# SM3.net
KiCad netlist of a schematic drawn in Altium Designer
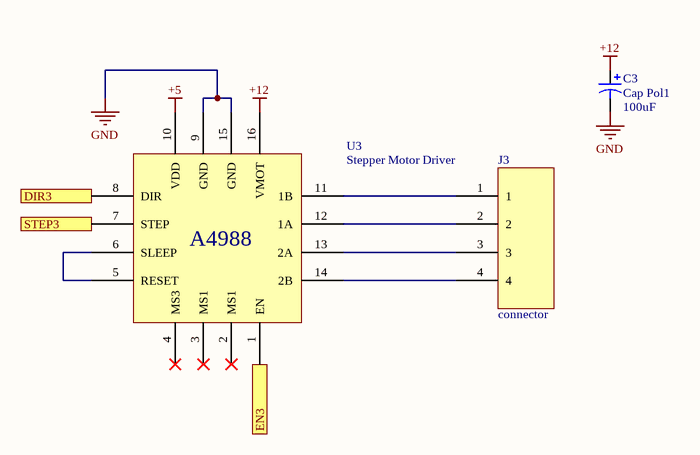
[diagram p0: SM3.SchDoc]

(export (version "E")
  (design (tool "Eeschema 10.0.6"))
  (components
    (comp (ref "C3")
      (value "Cap Pol1")
      (footprint "RB7.6-15")
      (description "Polarized Capacitor (Radial)")
      (fields (field (name "ALTIUM_VALUE") "100uF") (field (name "PUBLISHER") "Altium Limited"))
      (libsource (lib "Miscellaneous Devices") (part "Cap Pol1"))
    )
    (comp (ref "J3") (value "connector") (libsource (lib "Schlib") (part "JST_4P")))
    (comp (ref "U3") (value "Stepper Motor Driver") (libsource (lib "Schlib") (part "A4988")))
  )
  (nets
    (net (code "1") (name "+5") (class "Default")
      (node (ref "U3") (pin "10") (pinfunction "VDD_10") (pintype "passive"))
    )
    (net (code "2") (name "+12") (class "Default")
      (node (ref "C3") (pin "1") (pinfunction "1_1") (pintype "passive"))
      (node (ref "U3") (pin "16") (pinfunction "VMOT_16") (pintype "passive"))
    )
    (net (code "3") (name "/DIR3") (class "Default")
      (node (ref "U3") (pin "8") (pinfunction "DIR_8") (pintype "passive"))
    )
    (net (code "4") (name "/EN3") (class "Default")
      (node (ref "U3") (pin "1") (pinfunction "EN_1") (pintype "passive"))
    )
    (net (code "5") (name "/STEP3") (class "Default")
      (node (ref "U3") (pin "7") (pinfunction "STEP_7") (pintype "passive"))
    )
    (net (code "6") (name "GND") (class "Default")
      (node (ref "C3") (pin "2") (pinfunction "2_2") (pintype "passive"))
      (node (ref "U3") (pin "15") (pinfunction "GND_15") (pintype "passive"))
      (node (ref "U3") (pin "9") (pinfunction "GND_9") (pintype "passive"))
    )
    (net (code "7") (name "Net-(U3-1A)") (class "Default")
      (node (ref "J3") (pin "2") (pinfunction "2_2") (pintype "passive"))
      (node (ref "U3") (pin "12") (pinfunction "1A_12") (pintype "passive"))
    )
    (net (code "8") (name "Net-(U3-1B)") (class "Default")
      (node (ref "J3") (pin "1") (pinfunction "1_1") (pintype "passive"))
      (node (ref "U3") (pin "11") (pinfunction "1B_11") (pintype "passive"))
    )
    (net (code "9") (name "Net-(U3-2A)") (class "Default")
      (node (ref "J3") (pin "3") (pinfunction "3_3") (pintype "passive"))
      (node (ref "U3") (pin "13") (pinfunction "2A_13") (pintype "passive"))
    )
    (net (code "10") (name "Net-(U3-2B)") (class "Default")
      (node (ref "J3") (pin "4") (pinfunction "4_4") (pintype "passive"))
      (node (ref "U3") (pin "14") (pinfunction "2B_14") (pintype "passive"))
    )
    (net (code "11") (name "Net-(U3-RESET)") (class "Default")
      (node (ref "U3") (pin "5") (pinfunction "RESET_5") (pintype "passive"))
      (node (ref "U3") (pin "6") (pinfunction "SLEEP_6") (pintype "passive"))
    )
    (net (code "12") (name "unconnected-(U3-MS1-Pad2)") (class "Default")
      (node (ref "U3") (pin "2") (pinfunction "MS1_2") (pintype "passive+no_connect"))
    )
    (net (code "13") (name "unconnected-(U3-MS1-Pad3)") (class "Default")
      (node (ref "U3") (pin "3") (pinfunction "MS1_3") (pintype "passive+no_connect"))
    )
    (net (code "14") (name "unconnected-(U3-MS3-Pad4)") (class "Default")
      (node (ref "U3") (pin "4") (pinfunction "MS3_4") (pintype "passive+no_connect"))
    )
  )
)
